# Copy_of_Main.net
KiCad netlist of a schematic drawn in Altium Designer
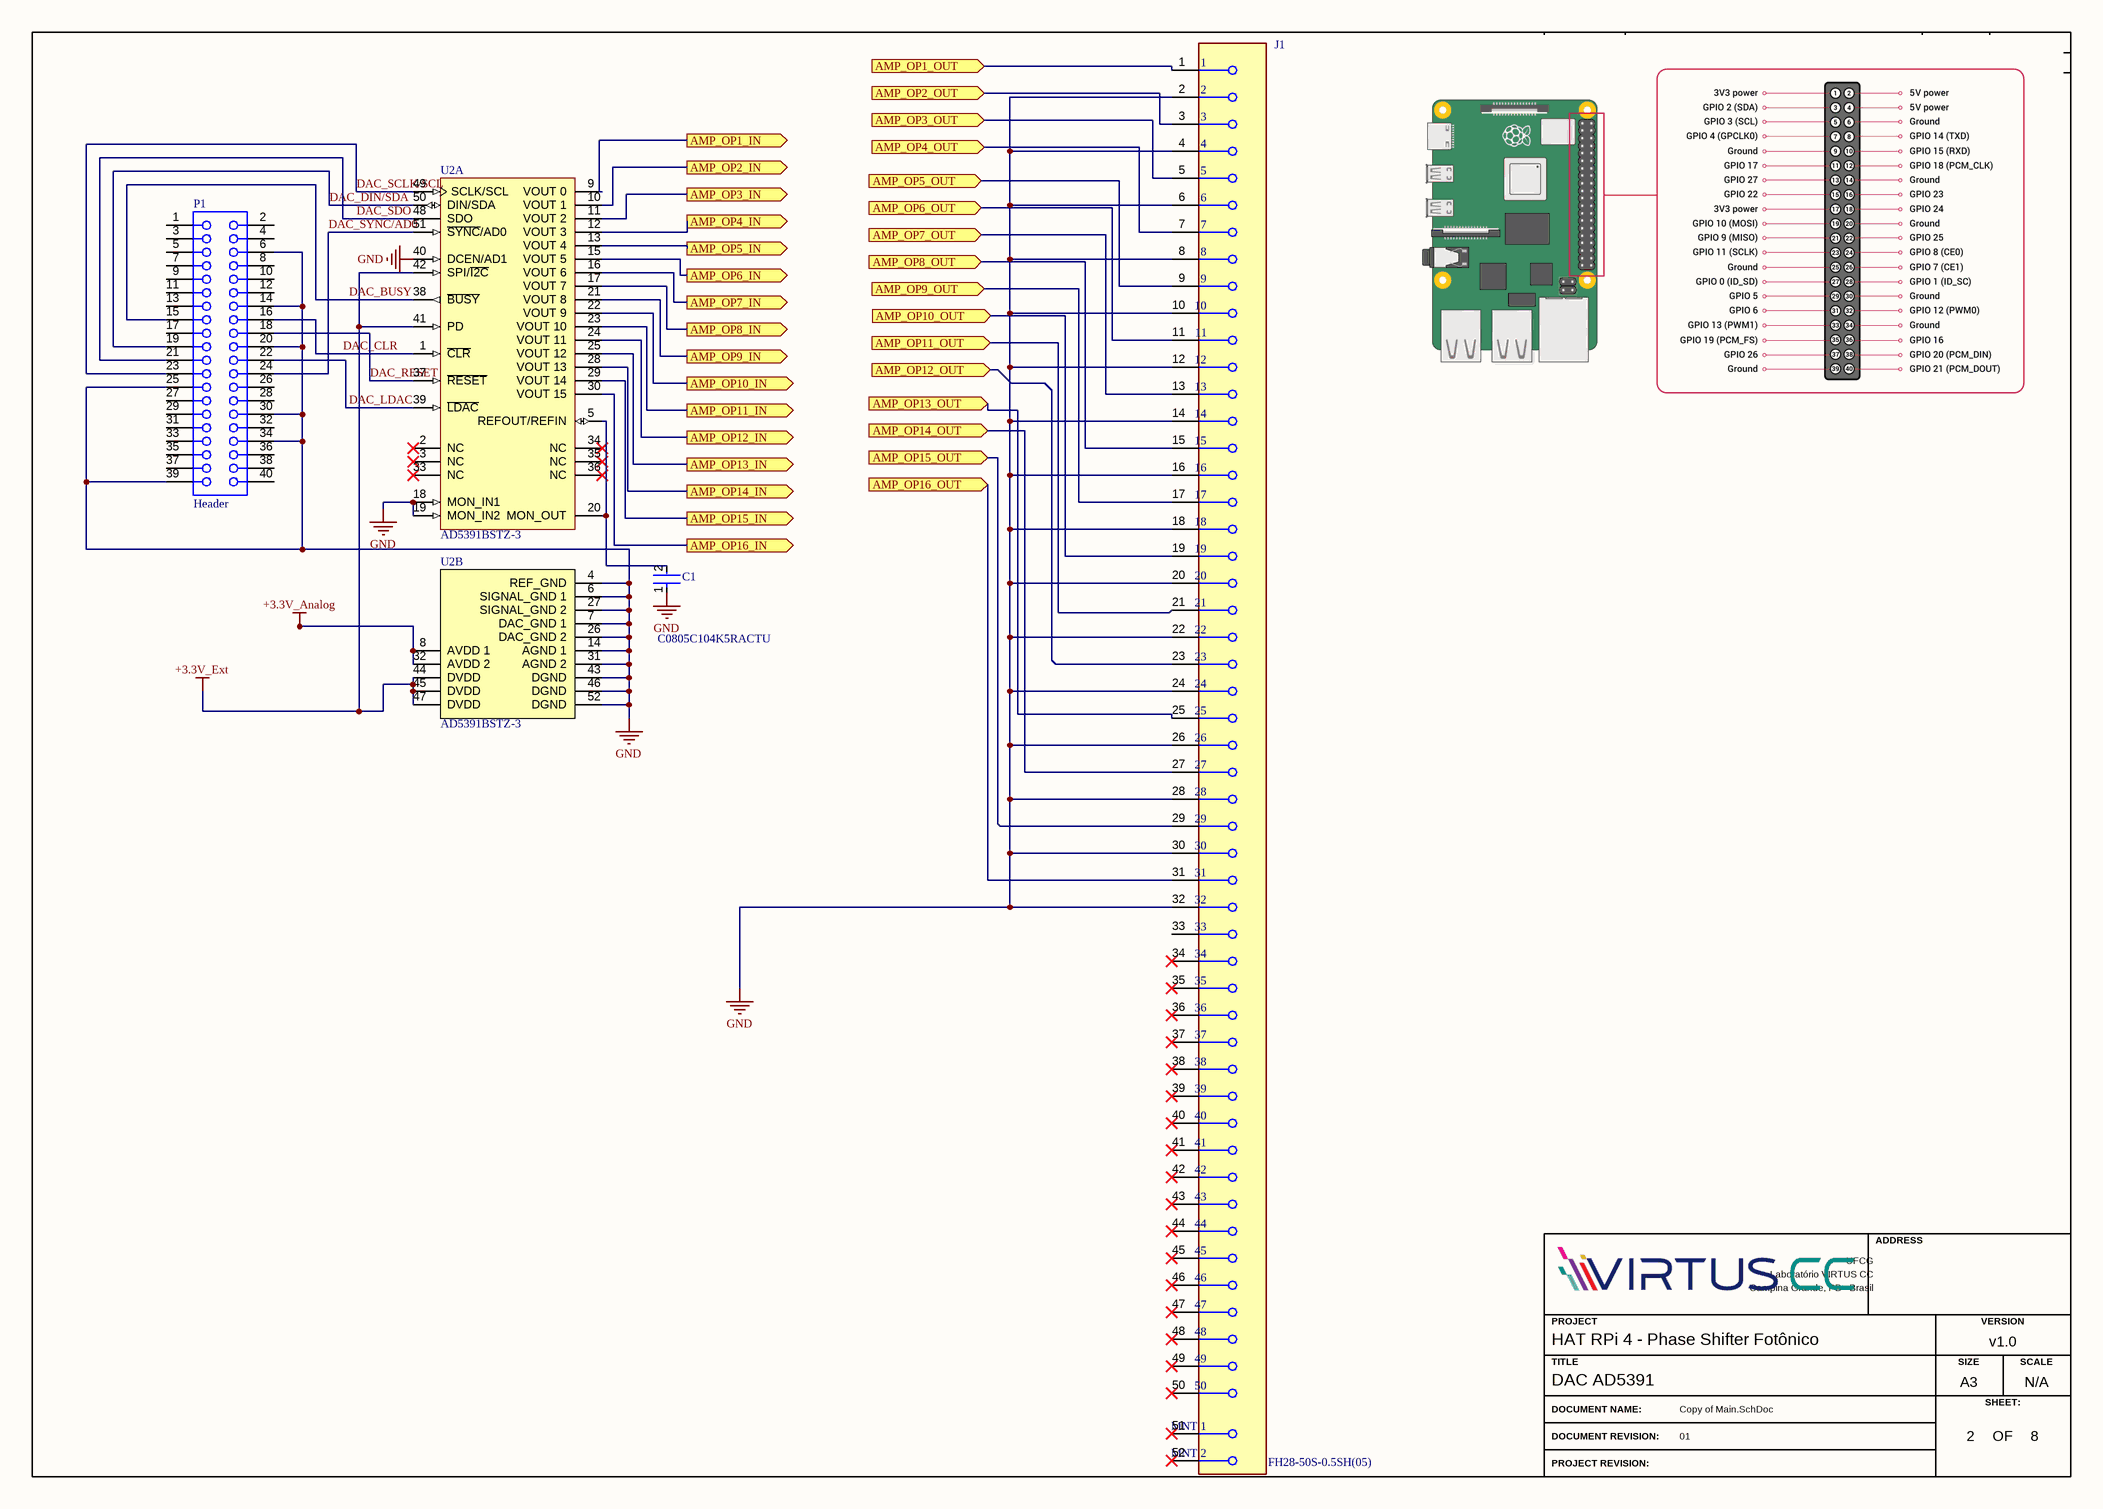
[diagram p0: Copy of Main.SchDoc]

(export (version "E")
  (design (tool "Eeschema 10.0.6"))
  (components
    (comp (ref "C1")
      (value "C0805C104K5RACTU")
      (footprint "FP-C0805C-DN-MFG")
      (description "CAP CER 0.1UF 50V X7R 0805")
      (fields
        (field (name "MANUFACTURER") "KEMET")
        (field (name "OCTOPART") "https://octopart.com/c0805c104k5ractu-kemet-143926")
      )
      (libsource (lib "Altium Content Vault") (part "b4654b650e69147ec39a6b967a45e02"))
    )
    (comp (ref "J1")
      (value "FH28-50S-0.5SH(05)")
      (footprint "FP-FH28-50S-0_5SH_05-MFG")
      (description "CONN FFC BOTTOM 50POS 0.50MM R/A")
      (fields
        (field (name "OCTOPART") "https://octopart.com/fh28-50s-0.5sh%2805%29-hirose-240232")
        (field (name "MANUFACTURER") "Hirose Electric Co Ltd")
      )
      (libsource (lib "Altium Content Vault") (part "b58b7e437d2d31add36c43a93be18f6"))
    )
    (comp (ref "P1")
      (value "Header")
      (footprint "61204021621")
      (description "THT Vertical Socket Header WR-PHD, Pitch 2.54 mm, Dual Row, 40 pins")
      (libsource (lib "Altium Content Vault") (part "Header_Female_2R_40P"))
    )
    (comp (ref "U2")
      (value "AD5391BSTZ-3")
      (footprint "ST-52_L")
      (fields (field (name "MANUFACTURER") "Analog Devices") (field (name "GENERIC PART NUMBER") "AD5391"))
      (libsource (lib "Altium Content Vault") (part "ADI-AD5391-ST-52"))
    )
  )
  (nets
    (net (code "1") (name "+3.3V_Analog") (class "Default")
      (node (ref "U2") (pin "32") (pinfunction "AVDD_2_32") (pintype "power_in"))
      (node (ref "U2") (pin "8") (pinfunction "AVDD_1_8") (pintype "power_in"))
    )
    (net (code "2") (name "+3.3V_Ext") (class "Default")
      (node (ref "U2") (pin "41") (pinfunction "PD_41") (pintype "input"))
      (node (ref "U2") (pin "42") (pinfunction "SPI/~{I2C}_42") (pintype "input"))
      (node (ref "U2") (pin "44") (pinfunction "DVDD_44") (pintype "power_in"))
      (node (ref "U2") (pin "45") (pinfunction "DVDD_45") (pintype "power_in"))
      (node (ref "U2") (pin "47") (pinfunction "DVDD_47") (pintype "power_in"))
    )
    (net (code "3") (name "/AMP_OP1_IN") (class "Default")
      (node (ref "U2") (pin "9") (pinfunction "VOUT_0_9") (pintype "tri_state"))
    )
    (net (code "4") (name "/AMP_OP1_OUT") (class "Default")
      (node (ref "J1") (pin "1") (pinfunction "1_1") (pintype "passive"))
    )
    (net (code "5") (name "/AMP_OP2_IN") (class "Default")
      (node (ref "U2") (pin "10") (pinfunction "VOUT_1_10") (pintype "tri_state"))
    )
    (net (code "6") (name "/AMP_OP2_OUT") (class "Default")
      (node (ref "J1") (pin "3") (pinfunction "3_3") (pintype "passive"))
    )
    (net (code "7") (name "/AMP_OP3_IN") (class "Default")
      (node (ref "U2") (pin "11") (pinfunction "VOUT_2_11") (pintype "tri_state"))
    )
    (net (code "8") (name "/AMP_OP3_OUT") (class "Default")
      (node (ref "J1") (pin "5") (pinfunction "5_5") (pintype "passive"))
    )
    (net (code "9") (name "/AMP_OP4_IN") (class "Default")
      (node (ref "U2") (pin "12") (pinfunction "VOUT_3_12") (pintype "tri_state"))
    )
    (net (code "10") (name "/AMP_OP4_OUT") (class "Default")
      (node (ref "J1") (pin "7") (pinfunction "7_7") (pintype "passive"))
    )
    (net (code "11") (name "/AMP_OP5_IN") (class "Default")
      (node (ref "U2") (pin "13") (pinfunction "VOUT_4_13") (pintype "tri_state"))
    )
    (net (code "12") (name "/AMP_OP5_OUT") (class "Default")
      (node (ref "J1") (pin "9") (pinfunction "9_9") (pintype "passive"))
    )
    (net (code "13") (name "/AMP_OP6_IN") (class "Default")
      (node (ref "U2") (pin "15") (pinfunction "VOUT_5_15") (pintype "tri_state"))
    )
    (net (code "14") (name "/AMP_OP6_OUT") (class "Default")
      (node (ref "J1") (pin "11") (pinfunction "11_11") (pintype "passive"))
    )
    (net (code "15") (name "/AMP_OP7_IN") (class "Default")
      (node (ref "U2") (pin "16") (pinfunction "VOUT_6_16") (pintype "tri_state"))
    )
    (net (code "16") (name "/AMP_OP7_OUT") (class "Default")
      (node (ref "J1") (pin "13") (pinfunction "13_13") (pintype "passive"))
    )
    (net (code "17") (name "/AMP_OP8_IN") (class "Default")
      (node (ref "U2") (pin "17") (pinfunction "VOUT_7_17") (pintype "tri_state"))
    )
    (net (code "18") (name "/AMP_OP8_OUT") (class "Default")
      (node (ref "J1") (pin "15") (pinfunction "15_15") (pintype "passive"))
    )
    (net (code "19") (name "/AMP_OP9_IN") (class "Default")
      (node (ref "U2") (pin "21") (pinfunction "VOUT_8_21") (pintype "tri_state"))
    )
    (net (code "20") (name "/AMP_OP9_OUT") (class "Default")
      (node (ref "J1") (pin "17") (pinfunction "17_17") (pintype "passive"))
    )
    (net (code "21") (name "/AMP_OP10_IN") (class "Default")
      (node (ref "U2") (pin "22") (pinfunction "VOUT_9_22") (pintype "tri_state"))
    )
    (net (code "22") (name "/AMP_OP10_OUT") (class "Default")
      (node (ref "J1") (pin "19") (pinfunction "19_19") (pintype "passive"))
    )
    (net (code "23") (name "/AMP_OP11_IN") (class "Default")
      (node (ref "U2") (pin "23") (pinfunction "VOUT_10_23") (pintype "tri_state"))
    )
    (net (code "24") (name "/AMP_OP11_OUT") (class "Default")
      (node (ref "J1") (pin "21") (pinfunction "21_21") (pintype "passive"))
    )
    (net (code "25") (name "/AMP_OP12_IN") (class "Default")
      (node (ref "U2") (pin "24") (pinfunction "VOUT_11_24") (pintype "tri_state"))
    )
    (net (code "26") (name "/AMP_OP12_OUT") (class "Default")
      (node (ref "J1") (pin "23") (pinfunction "23_23") (pintype "passive"))
    )
    (net (code "27") (name "/AMP_OP13_IN") (class "Default")
      (node (ref "U2") (pin "25") (pinfunction "VOUT_12_25") (pintype "tri_state"))
    )
    (net (code "28") (name "/AMP_OP13_OUT") (class "Default")
      (node (ref "J1") (pin "25") (pinfunction "25_25") (pintype "passive"))
    )
    (net (code "29") (name "/AMP_OP14_IN") (class "Default")
      (node (ref "U2") (pin "28") (pinfunction "VOUT_13_28") (pintype "tri_state"))
    )
    (net (code "30") (name "/AMP_OP14_OUT") (class "Default")
      (node (ref "J1") (pin "27") (pinfunction "27_27") (pintype "passive"))
    )
    (net (code "31") (name "/AMP_OP15_IN") (class "Default")
      (node (ref "U2") (pin "29") (pinfunction "VOUT_14_29") (pintype "tri_state"))
    )
    (net (code "32") (name "/AMP_OP15_OUT") (class "Default")
      (node (ref "J1") (pin "29") (pinfunction "29_29") (pintype "passive"))
    )
    (net (code "33") (name "/AMP_OP16_IN") (class "Default")
      (node (ref "U2") (pin "30") (pinfunction "VOUT_15_30") (pintype "tri_state"))
    )
    (net (code "34") (name "/AMP_OP16_OUT") (class "Default")
      (node (ref "J1") (pin "31") (pinfunction "31_31") (pintype "passive"))
    )
    (net (code "35") (name "/DAC_BUSY") (class "Default")
      (node (ref "P1") (pin "15") (pinfunction "15_15") (pintype "passive"))
      (node (ref "U2") (pin "38") (pinfunction "~{BUSY}_38") (pintype "output"))
    )
    (net (code "36") (name "/DAC_CLR") (class "Default")
      (node (ref "P1") (pin "16") (pinfunction "16_16") (pintype "passive"))
      (node (ref "U2") (pin "1") (pinfunction "~{CLR}_1") (pintype "input"))
    )
    (net (code "37") (name "/DAC_DIN{slash}SDA") (class "Default")
      (node (ref "P1") (pin "19") (pinfunction "19_19") (pintype "passive"))
      (node (ref "U2") (pin "50") (pinfunction "DIN/SDA_50") (pintype "bidirectional"))
    )
    (net (code "38") (name "/DAC_LDAC") (class "Default")
      (node (ref "P1") (pin "22") (pinfunction "22_22") (pintype "passive"))
      (node (ref "U2") (pin "39") (pinfunction "~{LDAC}_39") (pintype "input"))
    )
    (net (code "39") (name "/DAC_RESET") (class "Default")
      (node (ref "P1") (pin "18") (pinfunction "18_18") (pintype "passive"))
      (node (ref "U2") (pin "37") (pinfunction "~{RESET}_37") (pintype "input"))
    )
    (net (code "40") (name "/DAC_SCLK{slash}SCL") (class "Default")
      (node (ref "P1") (pin "23") (pinfunction "23_23") (pintype "passive"))
      (node (ref "U2") (pin "49") (pinfunction "SCLK/SCL_49") (pintype "input"))
    )
    (net (code "41") (name "/DAC_SDO") (class "Default")
      (node (ref "P1") (pin "21") (pinfunction "21_21") (pintype "passive"))
      (node (ref "U2") (pin "48") (pinfunction "SDO_48") (pintype "tri_state"))
    )
    (net (code "42") (name "/DAC_SYNC{slash}AD0") (class "Default")
      (node (ref "P1") (pin "24") (pinfunction "24_24") (pintype "passive"))
      (node (ref "U2") (pin "51") (pinfunction "~{SYNC}/AD0_51") (pintype "input"))
    )
    (net (code "43") (name "GND") (class "Default")
      (node (ref "C1") (pin "1") (pinfunction "1_1") (pintype "passive"))
      (node (ref "J1") (pin "10") (pinfunction "10_10") (pintype "passive"))
      (node (ref "J1") (pin "12") (pinfunction "12_12") (pintype "passive"))
      (node (ref "J1") (pin "14") (pinfunction "14_14") (pintype "passive"))
      (node (ref "J1") (pin "16") (pinfunction "16_16") (pintype "passive"))
      (node (ref "J1") (pin "18") (pinfunction "18_18") (pintype "passive"))
      (node (ref "J1") (pin "2") (pinfunction "2_2") (pintype "passive"))
      (node (ref "J1") (pin "20") (pinfunction "20_20") (pintype "passive"))
      (node (ref "J1") (pin "22") (pinfunction "22_22") (pintype "passive"))
      (node (ref "J1") (pin "24") (pinfunction "24_24") (pintype "passive"))
      (node (ref "J1") (pin "26") (pinfunction "26_26") (pintype "passive"))
      (node (ref "J1") (pin "28") (pinfunction "28_28") (pintype "passive"))
      (node (ref "J1") (pin "30") (pinfunction "30_30") (pintype "passive"))
      (node (ref "J1") (pin "32") (pinfunction "32_32") (pintype "passive"))
      (node (ref "J1") (pin "4") (pinfunction "4_4") (pintype "passive"))
      (node (ref "J1") (pin "6") (pinfunction "6_6") (pintype "passive"))
      (node (ref "J1") (pin "8") (pinfunction "8_8") (pintype "passive"))
      (node (ref "P1") (pin "14") (pinfunction "14_14") (pintype "passive"))
      (node (ref "P1") (pin "20") (pinfunction "20_20") (pintype "passive"))
      (node (ref "P1") (pin "25") (pinfunction "25_25") (pintype "passive"))
      (node (ref "P1") (pin "30") (pinfunction "30_30") (pintype "passive"))
      (node (ref "P1") (pin "34") (pinfunction "34_34") (pintype "passive"))
      (node (ref "P1") (pin "39") (pinfunction "39_39") (pintype "passive"))
      (node (ref "P1") (pin "6") (pinfunction "6_6") (pintype "passive"))
      (node (ref "U2") (pin "14") (pinfunction "AGND_1_14") (pintype "power_in"))
      (node (ref "U2") (pin "18") (pinfunction "MON_IN1_18") (pintype "input"))
      (node (ref "U2") (pin "19") (pinfunction "MON_IN2_19") (pintype "input"))
      (node (ref "U2") (pin "26") (pinfunction "DAC_GND_2_26") (pintype "power_in"))
      (node (ref "U2") (pin "27") (pinfunction "SIGNAL_GND_2_27") (pintype "power_in"))
      (node (ref "U2") (pin "31") (pinfunction "AGND_2_31") (pintype "power_in"))
      (node (ref "U2") (pin "4") (pinfunction "REF_GND_4") (pintype "power_in"))
      (node (ref "U2") (pin "40") (pinfunction "DCEN/AD1_40") (pintype "input"))
      (node (ref "U2") (pin "43") (pinfunction "DGND_43") (pintype "power_in"))
      (node (ref "U2") (pin "46") (pinfunction "DGND_46") (pintype "power_in"))
      (node (ref "U2") (pin "52") (pinfunction "DGND_52") (pintype "power_in"))
      (node (ref "U2") (pin "6") (pinfunction "SIGNAL_GND_1_6") (pintype "power_in"))
      (node (ref "U2") (pin "7") (pinfunction "DAC_GND_1_7") (pintype "power_in"))
    )
    (net (code "44") (name "Net-(U2A-MON_OUT)") (class "Default")
      (node (ref "C1") (pin "2") (pinfunction "2_2") (pintype "passive"))
      (node (ref "U2") (pin "20") (pinfunction "MON_OUT_20") (pintype "tri_state"))
      (node (ref "U2") (pin "5") (pinfunction "REFOUT/REFIN_5") (pintype "bidirectional"))
    )
    (net (code "45") (name "unconnected-(J1-MNT_1-Pad51)") (class "Default")
      (node (ref "J1") (pin "51") (pinfunction "MNT_1_51") (pintype "passive+no_connect"))
    )
    (net (code "46") (name "unconnected-(J1-MNT_2-Pad52)") (class "Default")
      (node (ref "J1") (pin "52") (pinfunction "MNT_2_52") (pintype "passive+no_connect"))
    )
    (net (code "47") (name "unconnected-(J1-Pad33)") (class "Default")
      (node (ref "J1") (pin "33") (pinfunction "33_33") (pintype "passive"))
    )
    (net (code "48") (name "unconnected-(J1-Pad34)") (class "Default")
      (node (ref "J1") (pin "34") (pinfunction "34_34") (pintype "passive+no_connect"))
    )
    (net (code "49") (name "unconnected-(J1-Pad35)") (class "Default")
      (node (ref "J1") (pin "35") (pinfunction "35_35") (pintype "passive+no_connect"))
    )
    (net (code "50") (name "unconnected-(J1-Pad36)") (class "Default")
      (node (ref "J1") (pin "36") (pinfunction "36_36") (pintype "passive+no_connect"))
    )
    (net (code "51") (name "unconnected-(J1-Pad37)") (class "Default")
      (node (ref "J1") (pin "37") (pinfunction "37_37") (pintype "passive+no_connect"))
    )
    (net (code "52") (name "unconnected-(J1-Pad38)") (class "Default")
      (node (ref "J1") (pin "38") (pinfunction "38_38") (pintype "passive+no_connect"))
    )
    (net (code "53") (name "unconnected-(J1-Pad39)") (class "Default")
      (node (ref "J1") (pin "39") (pinfunction "39_39") (pintype "passive+no_connect"))
    )
    (net (code "54") (name "unconnected-(J1-Pad40)") (class "Default")
      (node (ref "J1") (pin "40") (pinfunction "40_40") (pintype "passive+no_connect"))
    )
    (net (code "55") (name "unconnected-(J1-Pad41)") (class "Default")
      (node (ref "J1") (pin "41") (pinfunction "41_41") (pintype "passive+no_connect"))
    )
    (net (code "56") (name "unconnected-(J1-Pad42)") (class "Default")
      (node (ref "J1") (pin "42") (pinfunction "42_42") (pintype "passive+no_connect"))
    )
    (net (code "57") (name "unconnected-(J1-Pad43)") (class "Default")
      (node (ref "J1") (pin "43") (pinfunction "43_43") (pintype "passive+no_connect"))
    )
    (net (code "58") (name "unconnected-(J1-Pad44)") (class "Default")
      (node (ref "J1") (pin "44") (pinfunction "44_44") (pintype "passive+no_connect"))
    )
    (net (code "59") (name "unconnected-(J1-Pad45)") (class "Default")
      (node (ref "J1") (pin "45") (pinfunction "45_45") (pintype "passive+no_connect"))
    )
    (net (code "60") (name "unconnected-(J1-Pad46)") (class "Default")
      (node (ref "J1") (pin "46") (pinfunction "46_46") (pintype "passive+no_connect"))
    )
    (net (code "61") (name "unconnected-(J1-Pad47)") (class "Default")
      (node (ref "J1") (pin "47") (pinfunction "47_47") (pintype "passive+no_connect"))
    )
    (net (code "62") (name "unconnected-(J1-Pad48)") (class "Default")
      (node (ref "J1") (pin "48") (pinfunction "48_48") (pintype "passive+no_connect"))
    )
    (net (code "63") (name "unconnected-(J1-Pad49)") (class "Default")
      (node (ref "J1") (pin "49") (pinfunction "49_49") (pintype "passive+no_connect"))
    )
    (net (code "64") (name "unconnected-(J1-Pad50)") (class "Default")
      (node (ref "J1") (pin "50") (pinfunction "50_50") (pintype "passive+no_connect"))
    )
    (net (code "65") (name "unconnected-(P1-Pad1)") (class "Default")
      (node (ref "P1") (pin "1") (pinfunction "1_1") (pintype "passive"))
    )
    (net (code "66") (name "unconnected-(P1-Pad2)") (class "Default")
      (node (ref "P1") (pin "2") (pinfunction "2_2") (pintype "passive"))
    )
    (net (code "67") (name "unconnected-(P1-Pad3)") (class "Default")
      (node (ref "P1") (pin "3") (pinfunction "3_3") (pintype "passive"))
    )
    (net (code "68") (name "unconnected-(P1-Pad4)") (class "Default")
      (node (ref "P1") (pin "4") (pinfunction "4_4") (pintype "passive"))
    )
    (net (code "69") (name "unconnected-(P1-Pad5)") (class "Default")
      (node (ref "P1") (pin "5") (pinfunction "5_5") (pintype "passive"))
    )
    (net (code "70") (name "unconnected-(P1-Pad7)") (class "Default")
      (node (ref "P1") (pin "7") (pinfunction "7_7") (pintype "passive"))
    )
    (net (code "71") (name "unconnected-(P1-Pad8)") (class "Default")
      (node (ref "P1") (pin "8") (pinfunction "8_8") (pintype "passive"))
    )
    (net (code "72") (name "unconnected-(P1-Pad9)") (class "Default")
      (node (ref "P1") (pin "9") (pinfunction "9_9") (pintype "passive"))
    )
    (net (code "73") (name "unconnected-(P1-Pad10)") (class "Default")
      (node (ref "P1") (pin "10") (pinfunction "10_10") (pintype "passive"))
    )
    (net (code "74") (name "unconnected-(P1-Pad11)") (class "Default")
      (node (ref "P1") (pin "11") (pinfunction "11_11") (pintype "passive"))
    )
    (net (code "75") (name "unconnected-(P1-Pad12)") (class "Default")
      (node (ref "P1") (pin "12") (pinfunction "12_12") (pintype "passive"))
    )
    (net (code "76") (name "unconnected-(P1-Pad13)") (class "Default")
      (node (ref "P1") (pin "13") (pinfunction "13_13") (pintype "passive"))
    )
    (net (code "77") (name "unconnected-(P1-Pad17)") (class "Default")
      (node (ref "P1") (pin "17") (pinfunction "17_17") (pintype "passive"))
    )
    (net (code "78") (name "unconnected-(P1-Pad26)") (class "Default")
      (node (ref "P1") (pin "26") (pinfunction "26_26") (pintype "passive"))
    )
    (net (code "79") (name "unconnected-(P1-Pad27)") (class "Default")
      (node (ref "P1") (pin "27") (pinfunction "27_27") (pintype "passive"))
    )
    (net (code "80") (name "unconnected-(P1-Pad28)") (class "Default")
      (node (ref "P1") (pin "28") (pinfunction "28_28") (pintype "passive"))
    )
    (net (code "81") (name "unconnected-(P1-Pad29)") (class "Default")
      (node (ref "P1") (pin "29") (pinfunction "29_29") (pintype "passive"))
    )
    (net (code "82") (name "unconnected-(P1-Pad31)") (class "Default")
      (node (ref "P1") (pin "31") (pinfunction "31_31") (pintype "passive"))
    )
    (net (code "83") (name "unconnected-(P1-Pad32)") (class "Default")
      (node (ref "P1") (pin "32") (pinfunction "32_32") (pintype "passive"))
    )
    (net (code "84") (name "unconnected-(P1-Pad33)") (class "Default")
      (node (ref "P1") (pin "33") (pinfunction "33_33") (pintype "passive"))
    )
    (net (code "85") (name "unconnected-(P1-Pad35)") (class "Default")
      (node (ref "P1") (pin "35") (pinfunction "35_35") (pintype "passive"))
    )
    (net (code "86") (name "unconnected-(P1-Pad36)") (class "Default")
      (node (ref "P1") (pin "36") (pinfunction "36_36") (pintype "passive"))
    )
    (net (code "87") (name "unconnected-(P1-Pad37)") (class "Default")
      (node (ref "P1") (pin "37") (pinfunction "37_37") (pintype "passive"))
    )
    (net (code "88") (name "unconnected-(P1-Pad38)") (class "Default")
      (node (ref "P1") (pin "38") (pinfunction "38_38") (pintype "passive"))
    )
    (net (code "89") (name "unconnected-(P1-Pad40)") (class "Default")
      (node (ref "P1") (pin "40") (pinfunction "40_40") (pintype "passive"))
    )
    (net (code "90") (name "unconnected-(U2A-NC-Pad2)") (class "Default")
      (node (ref "U2") (pin "2") (pinfunction "NC_2") (pintype "passive+no_connect"))
    )
    (net (code "91") (name "unconnected-(U2A-NC-Pad3)") (class "Default")
      (node (ref "U2") (pin "3") (pinfunction "NC_3") (pintype "passive+no_connect"))
    )
    (net (code "92") (name "unconnected-(U2A-NC-Pad33)") (class "Default")
      (node (ref "U2") (pin "33") (pinfunction "NC_33") (pintype "passive+no_connect"))
    )
    (net (code "93") (name "unconnected-(U2A-NC-Pad34)") (class "Default")
      (node (ref "U2") (pin "34") (pinfunction "NC_34") (pintype "passive+no_connect"))
    )
    (net (code "94") (name "unconnected-(U2A-NC-Pad35)") (class "Default")
      (node (ref "U2") (pin "35") (pinfunction "NC_35") (pintype "passive+no_connect"))
    )
    (net (code "95") (name "unconnected-(U2A-NC-Pad36)") (class "Default")
      (node (ref "U2") (pin "36") (pinfunction "NC_36") (pintype "passive+no_connect"))
    )
  )
)
